# PCM2704_Test_v1.net
KiCad netlist of a schematic drawn in EAGLE
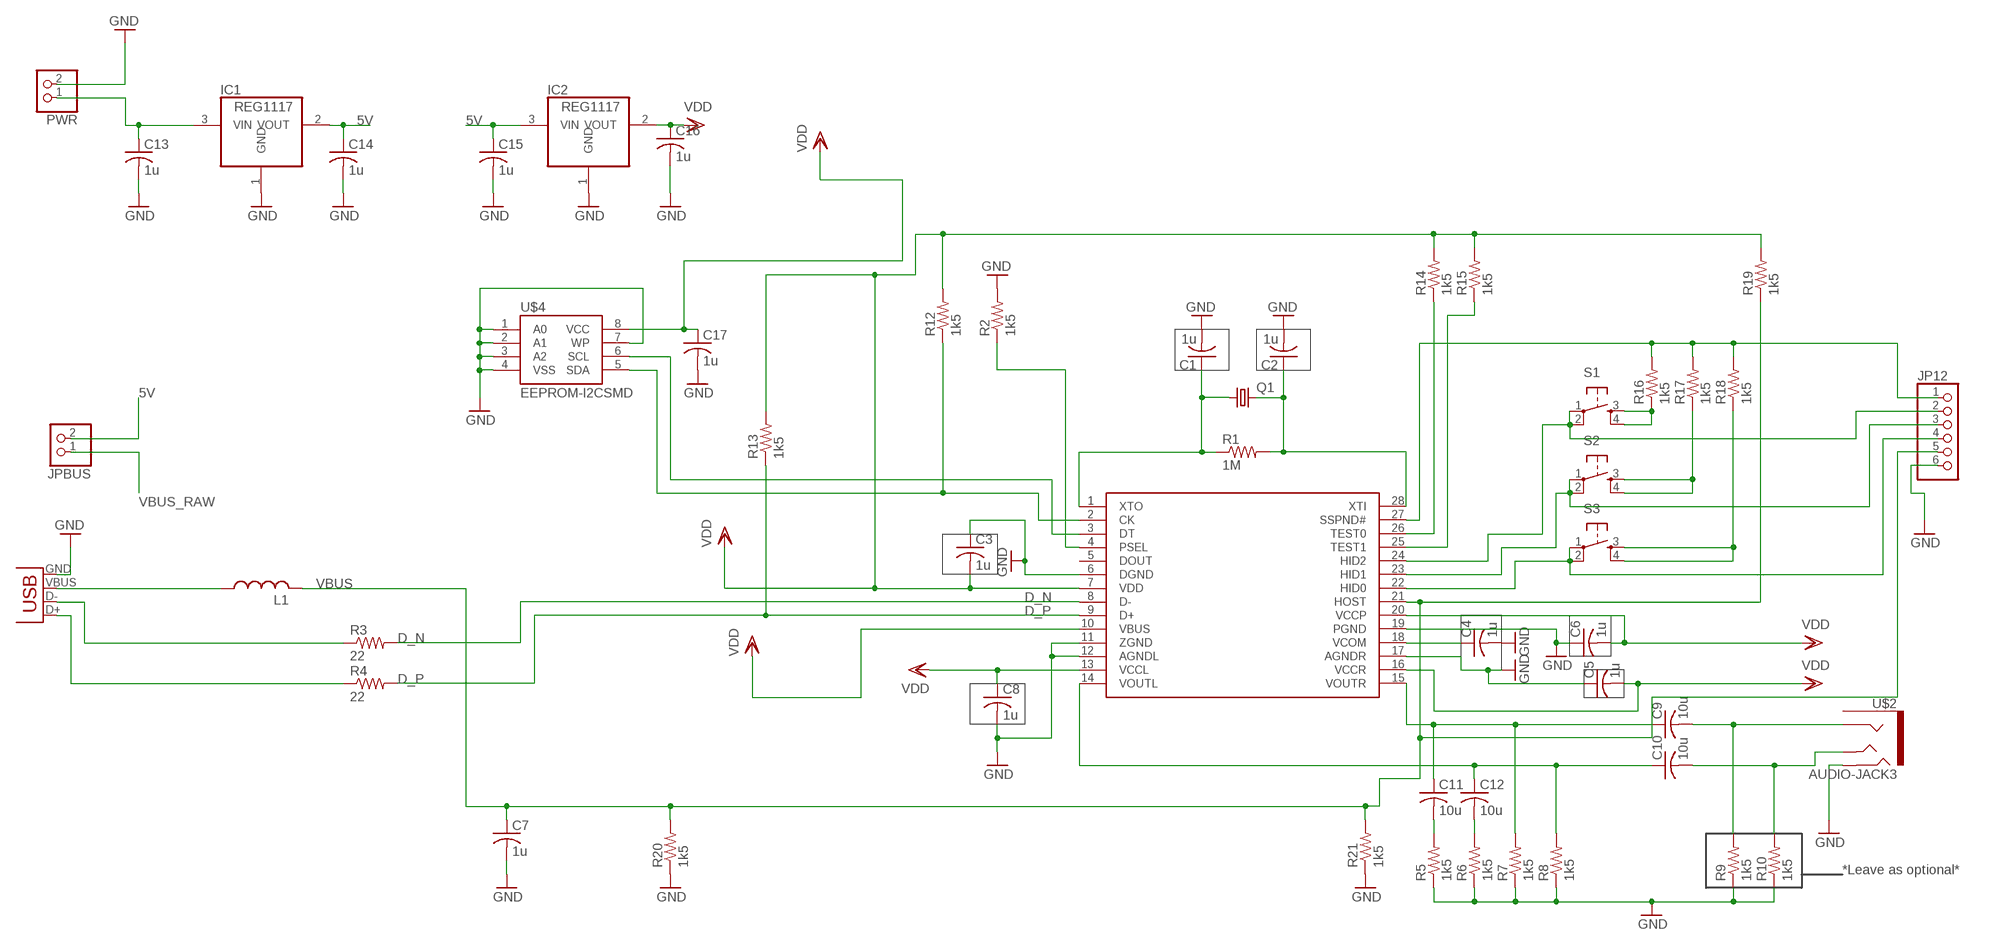
[diagram p0: schematic, sheet 1]

(export (version "E")
  (design (tool "Eeschema 10.0.6"))
  (components
    (comp (ref "C1")
      (value "1u")
      (footprint "eagle-import:C0402")
      (libsource (lib "eagle-import") (part "C-USC0402"))
    )
    (comp (ref "C2")
      (value "1u")
      (footprint "eagle-import:C0402")
      (libsource (lib "eagle-import") (part "C-USC0402"))
    )
    (comp (ref "C3")
      (value "1u")
      (footprint "eagle-import:C0402")
      (libsource (lib "eagle-import") (part "C-USC0402"))
    )
    (comp (ref "C4")
      (value "1u")
      (footprint "eagle-import:C0402")
      (libsource (lib "eagle-import") (part "C-USC0402"))
    )
    (comp (ref "C5")
      (value "1u")
      (footprint "eagle-import:C0402")
      (libsource (lib "eagle-import") (part "C-USC0402"))
    )
    (comp (ref "C6")
      (value "1u")
      (footprint "eagle-import:C0402")
      (libsource (lib "eagle-import") (part "C-USC0402"))
    )
    (comp (ref "C7")
      (value "1u")
      (footprint "eagle-import:C0402")
      (libsource (lib "eagle-import") (part "C-USC0402"))
    )
    (comp (ref "C8")
      (value "1u")
      (footprint "eagle-import:C0402")
      (libsource (lib "eagle-import") (part "C-USC0402"))
    )
    (comp (ref "C9")
      (value "10u")
      (footprint "eagle-import:C0805")
      (libsource (lib "eagle-import") (part "C-USC0805"))
    )
    (comp (ref "C10")
      (value "10u")
      (footprint "eagle-import:C0805")
      (libsource (lib "eagle-import") (part "C-USC0805"))
    )
    (comp (ref "C11")
      (value "10u")
      (footprint "eagle-import:C0805")
      (libsource (lib "eagle-import") (part "C-USC0805"))
    )
    (comp (ref "C12")
      (value "10u")
      (footprint "eagle-import:C0805")
      (libsource (lib "eagle-import") (part "C-USC0805"))
    )
    (comp (ref "C13")
      (value "1u")
      (footprint "eagle-import:C0805")
      (libsource (lib "eagle-import") (part "C-USC0805"))
    )
    (comp (ref "C14")
      (value "1u")
      (footprint "eagle-import:C0805")
      (libsource (lib "eagle-import") (part "C-USC0805"))
    )
    (comp (ref "C15")
      (value "1u")
      (footprint "eagle-import:C0805")
      (libsource (lib "eagle-import") (part "C-USC0805"))
    )
    (comp (ref "C16")
      (value "1u")
      (footprint "eagle-import:C0805")
      (libsource (lib "eagle-import") (part "C-USC0805"))
    )
    (comp (ref "C17")
      (value "1u")
      (footprint "eagle-import:C0402")
      (libsource (lib "eagle-import") (part "C-USC0402"))
    )
    (comp (ref "IC1")
      (value "REG1117")
      (footprint "eagle-import:SOT223")
      (libsource (lib "eagle-import") (part "REG1117"))
    )
    (comp (ref "IC2")
      (value "REG1117")
      (footprint "eagle-import:SOT223")
      (libsource (lib "eagle-import") (part "REG1117"))
    )
    (comp (ref "JP12")
      (value "PINHD-1X6")
      (footprint "eagle-import:1X06")
      (libsource (lib "eagle-import") (part "PINHD-1X6"))
    )
    (comp (ref "JPBUS")
      (value "PINHD-1X2")
      (footprint "eagle-import:1X02")
      (libsource (lib "eagle-import") (part "PINHD-1X2"))
    )
    (comp (ref "L1")
      (value "L-USL3225M")
      (footprint "eagle-import:L3225M")
      (libsource (lib "eagle-import") (part "L-USL3225M"))
    )
    (comp (ref "PWR")
      (value "PINHD-1X2")
      (footprint "eagle-import:1X02")
      (libsource (lib "eagle-import") (part "PINHD-1X2"))
    )
    (comp (ref "Q1")
      (value "CRYSTALHC49US")
      (footprint "eagle-import:HC49US")
      (libsource (lib "eagle-import") (part "CRYSTALHC49US"))
    )
    (comp (ref "R1")
      (value "1M")
      (footprint "eagle-import:R0603")
      (libsource (lib "eagle-import") (part "R-US_R0603"))
    )
    (comp (ref "R2")
      (value "1k5")
      (footprint "eagle-import:R0603")
      (libsource (lib "eagle-import") (part "R-US_R0603"))
    )
    (comp (ref "R3")
      (value "22")
      (footprint "eagle-import:R0603")
      (libsource (lib "eagle-import") (part "R-US_R0603"))
    )
    (comp (ref "R4")
      (value "22")
      (footprint "eagle-import:R0603")
      (libsource (lib "eagle-import") (part "R-US_R0603"))
    )
    (comp (ref "R5")
      (value "1k5")
      (footprint "eagle-import:R0805")
      (libsource (lib "eagle-import") (part "R-US_R0805"))
    )
    (comp (ref "R6")
      (value "1k5")
      (footprint "eagle-import:R0805")
      (libsource (lib "eagle-import") (part "R-US_R0805"))
    )
    (comp (ref "R7")
      (value "1k5")
      (footprint "eagle-import:R0805")
      (libsource (lib "eagle-import") (part "R-US_R0805"))
    )
    (comp (ref "R8")
      (value "1k5")
      (footprint "eagle-import:R0805")
      (libsource (lib "eagle-import") (part "R-US_R0805"))
    )
    (comp (ref "R9")
      (value "1k5")
      (footprint "eagle-import:R0805")
      (libsource (lib "eagle-import") (part "R-US_R0805"))
    )
    (comp (ref "R10")
      (value "1k5")
      (footprint "eagle-import:R0805")
      (libsource (lib "eagle-import") (part "R-US_R0805"))
    )
    (comp (ref "R12")
      (value "1k5")
      (footprint "eagle-import:R0603")
      (libsource (lib "eagle-import") (part "R-US_R0603"))
    )
    (comp (ref "R13")
      (value "1k5")
      (footprint "eagle-import:R0603")
      (libsource (lib "eagle-import") (part "R-US_R0603"))
    )
    (comp (ref "R14")
      (value "1k5")
      (footprint "eagle-import:R0603")
      (libsource (lib "eagle-import") (part "R-US_R0603"))
    )
    (comp (ref "R15")
      (value "1k5")
      (footprint "eagle-import:R0603")
      (libsource (lib "eagle-import") (part "R-US_R0603"))
    )
    (comp (ref "R16")
      (value "1k5")
      (footprint "eagle-import:R0603")
      (libsource (lib "eagle-import") (part "R-US_R0603"))
    )
    (comp (ref "R17")
      (value "1k5")
      (footprint "eagle-import:R0603")
      (libsource (lib "eagle-import") (part "R-US_R0603"))
    )
    (comp (ref "R18")
      (value "1k5")
      (footprint "eagle-import:R0603")
      (libsource (lib "eagle-import") (part "R-US_R0603"))
    )
    (comp (ref "R19")
      (value "1k5")
      (footprint "eagle-import:R0603")
      (libsource (lib "eagle-import") (part "R-US_R0603"))
    )
    (comp (ref "R20")
      (value "1k5")
      (footprint "eagle-import:R0603")
      (libsource (lib "eagle-import") (part "R-US_R0603"))
    )
    (comp (ref "R21")
      (value "1k5")
      (footprint "eagle-import:R0603")
      (libsource (lib "eagle-import") (part "R-US_R0603"))
    )
    (comp (ref "S1")
      (value "TAC_SWITCHSMD")
      (footprint "eagle-import:TACTILE_SWITCH_SMD")
      (libsource (lib "eagle-import") (part "TAC_SWITCHSMD"))
    )
    (comp (ref "S2")
      (value "TAC_SWITCHSMD")
      (footprint "eagle-import:TACTILE_SWITCH_SMD")
      (libsource (lib "eagle-import") (part "TAC_SWITCHSMD"))
    )
    (comp (ref "S3")
      (value "TAC_SWITCHSMD")
      (footprint "eagle-import:TACTILE_SWITCH_SMD")
      (libsource (lib "eagle-import") (part "TAC_SWITCHSMD"))
    )
    (comp (ref "U$1")
      (value "PCM2704C")
      (footprint "eagle-import:PCM2704C")
      (libsource (lib "eagle-import") (part "PCM2704C"))
    )
    (comp (ref "U$2")
      (value "AUDIO-JACK3")
      (footprint "eagle-import:AUDIO-JACK-TRRS-SMD")
      (libsource (lib "eagle-import") (part "AUDIO-JACK3"))
    )
    (comp (ref "U$4")
      (value "EEPROM-I2CSMD")
      (footprint "eagle-import:SO08")
      (libsource (lib "eagle-import") (part "EEPROM-I2CSMD"))
    )
    (comp (ref "X1")
      (value "USB-MB-S")
      (footprint "eagle-import:USB-MB-S")
      (libsource (lib "eagle-import") (part "USB-MB-S"))
    )
  )
  (nets
    (net (code "1") (name "/5V") (class "Default")
      (node (ref "C14") (pin "1") (pinfunction "1_1") (pintype "passive"))
      (node (ref "C15") (pin "1") (pinfunction "1_1") (pintype "passive"))
      (node (ref "IC1") (pin "2") (pinfunction "VOUT_2") (pintype "output"))
      (node (ref "IC2") (pin "3") (pinfunction "VIN_3") (pintype "input"))
      (node (ref "JPBUS") (pin "2") (pinfunction "2_2") (pintype "passive"))
    )
    (net (code "2") (name "/D_N") (class "Default")
      (node (ref "R3") (pin "2") (pinfunction "2_2") (pintype "passive"))
      (node (ref "U$1") (pin "8") (pinfunction "D-_8") (pintype "bidirectional"))
    )
    (net (code "3") (name "/D_P") (class "Default")
      (node (ref "R13") (pin "1") (pinfunction "1_1") (pintype "passive"))
      (node (ref "R4") (pin "2") (pinfunction "2_2") (pintype "passive"))
      (node (ref "U$1") (pin "9") (pinfunction "D+_9") (pintype "bidirectional"))
    )
    (net (code "4") (name "/VBUS") (class "Default")
      (node (ref "C7") (pin "1") (pinfunction "1_1") (pintype "passive"))
      (node (ref "JP12") (pin "5") (pinfunction "5_5") (pintype "passive"))
      (node (ref "L1") (pin "2") (pinfunction "2_2") (pintype "passive"))
      (node (ref "R19") (pin "1") (pinfunction "1_1") (pintype "passive"))
      (node (ref "R20") (pin "2") (pinfunction "2_2") (pintype "passive"))
      (node (ref "R21") (pin "2") (pinfunction "2_2") (pintype "passive"))
      (node (ref "U$1") (pin "21") (pinfunction "HOST_21") (pintype "bidirectional"))
    )
    (net (code "5") (name "/VBUS_RAW") (class "Default")
      (node (ref "JPBUS") (pin "1") (pinfunction "1_1") (pintype "passive"))
      (node (ref "L1") (pin "1") (pinfunction "1_1") (pintype "passive"))
      (node (ref "X1") (pin "VBUS") (pinfunction "VBUS_VBUS") (pintype "bidirectional"))
    )
    (net (code "6") (name "GND") (class "Default")
      (node (ref "C1") (pin "2") (pinfunction "2_2") (pintype "passive"))
      (node (ref "C13") (pin "2") (pinfunction "2_2") (pintype "passive"))
      (node (ref "C14") (pin "2") (pinfunction "2_2") (pintype "passive"))
      (node (ref "C15") (pin "2") (pinfunction "2_2") (pintype "passive"))
      (node (ref "C16") (pin "2") (pinfunction "2_2") (pintype "passive"))
      (node (ref "C17") (pin "2") (pinfunction "2_2") (pintype "passive"))
      (node (ref "C2") (pin "2") (pinfunction "2_2") (pintype "passive"))
      (node (ref "C3") (pin "1") (pinfunction "1_1") (pintype "passive"))
      (node (ref "C4") (pin "2") (pinfunction "2_2") (pintype "passive"))
      (node (ref "C5") (pin "1") (pinfunction "1_1") (pintype "passive"))
      (node (ref "C6") (pin "1") (pinfunction "1_1") (pintype "passive"))
      (node (ref "C7") (pin "2") (pinfunction "2_2") (pintype "passive"))
      (node (ref "C8") (pin "2") (pinfunction "2_2") (pintype "passive"))
      (node (ref "IC1") (pin "1") (pinfunction "GND_1") (pintype "power_in"))
      (node (ref "IC2") (pin "1") (pinfunction "GND_1") (pintype "power_in"))
      (node (ref "JP12") (pin "6") (pinfunction "6_6") (pintype "passive"))
      (node (ref "PWR") (pin "2") (pinfunction "2_2") (pintype "passive"))
      (node (ref "R10") (pin "1") (pinfunction "1_1") (pintype "passive"))
      (node (ref "R2") (pin "2") (pinfunction "2_2") (pintype "passive"))
      (node (ref "R20") (pin "1") (pinfunction "1_1") (pintype "passive"))
      (node (ref "R21") (pin "1") (pinfunction "1_1") (pintype "passive"))
      (node (ref "R5") (pin "1") (pinfunction "1_1") (pintype "passive"))
      (node (ref "R6") (pin "1") (pinfunction "1_1") (pintype "passive"))
      (node (ref "R7") (pin "1") (pinfunction "1_1") (pintype "passive"))
      (node (ref "R8") (pin "1") (pinfunction "1_1") (pintype "passive"))
      (node (ref "R9") (pin "1") (pinfunction "1_1") (pintype "passive"))
      (node (ref "U$1") (pin "11") (pinfunction "ZGND_11") (pintype "bidirectional"))
      (node (ref "U$1") (pin "12") (pinfunction "AGNDL_12") (pintype "bidirectional"))
      (node (ref "U$1") (pin "17") (pinfunction "AGNDR_17") (pintype "bidirectional"))
      (node (ref "U$1") (pin "19") (pinfunction "PGND_19") (pintype "bidirectional"))
      (node (ref "U$1") (pin "6") (pinfunction "DGND_6") (pintype "bidirectional"))
      (node (ref "U$2") (pin "RING2") (pinfunction "RING2_RING2") (pintype "bidirectional"))
      (node (ref "U$4") (pin "1") (pinfunction "A0_1") (pintype "bidirectional"))
      (node (ref "U$4") (pin "2") (pinfunction "A1_2") (pintype "bidirectional"))
      (node (ref "U$4") (pin "3") (pinfunction "A2_3") (pintype "bidirectional"))
      (node (ref "U$4") (pin "4") (pinfunction "VSS_4") (pintype "power_in"))
      (node (ref "U$4") (pin "7") (pinfunction "WP_7") (pintype "bidirectional"))
      (node (ref "X1") (pin "GND") (pinfunction "GND_GND") (pintype "bidirectional"))
    )
    (net (code "7") (name "Net-(C9-Pad2)") (class "Default")
      (node (ref "C9") (pin "2") (pinfunction "2_2") (pintype "passive"))
      (node (ref "R9") (pin "2") (pinfunction "2_2") (pintype "passive"))
      (node (ref "U$2") (pin "RING1") (pinfunction "RING1_RING1") (pintype "bidirectional"))
    )
    (net (code "8") (name "Net-(C10-Pad2)") (class "Default")
      (node (ref "C10") (pin "2") (pinfunction "2_2") (pintype "passive"))
      (node (ref "R10") (pin "2") (pinfunction "2_2") (pintype "passive"))
      (node (ref "U$2") (pin "TIP") (pinfunction "TIP_TIP") (pintype "bidirectional"))
    )
    (net (code "9") (name "Net-(C11-Pad2)") (class "Default")
      (node (ref "C11") (pin "2") (pinfunction "2_2") (pintype "passive"))
      (node (ref "R5") (pin "2") (pinfunction "2_2") (pintype "passive"))
    )
    (net (code "10") (name "Net-(C12-Pad2)") (class "Default")
      (node (ref "C12") (pin "2") (pinfunction "2_2") (pintype "passive"))
      (node (ref "R6") (pin "2") (pinfunction "2_2") (pintype "passive"))
    )
    (net (code "11") (name "Net-(IC1-VIN)") (class "Default")
      (node (ref "C13") (pin "1") (pinfunction "1_1") (pintype "passive"))
      (node (ref "IC1") (pin "3") (pinfunction "VIN_3") (pintype "input"))
      (node (ref "PWR") (pin "1") (pinfunction "1_1") (pintype "passive"))
    )
    (net (code "12") (name "Net-(R3-Pad1)") (class "Default")
      (node (ref "R3") (pin "1") (pinfunction "1_1") (pintype "passive"))
      (node (ref "X1") (pin "D-") (pinfunction "D-_D-") (pintype "bidirectional"))
    )
    (net (code "13") (name "Net-(R4-Pad1)") (class "Default")
      (node (ref "R4") (pin "1") (pinfunction "1_1") (pintype "passive"))
      (node (ref "X1") (pin "D+") (pinfunction "D+_D+") (pintype "bidirectional"))
    )
    (net (code "14") (name "Net-(R16-Pad1)") (class "Default")
      (node (ref "R16") (pin "1") (pinfunction "1_1") (pintype "passive"))
      (node (ref "S1") (pin "3") (pinfunction "3_3") (pintype "passive"))
      (node (ref "S1") (pin "4") (pinfunction "4_4") (pintype "passive"))
    )
    (net (code "15") (name "Net-(R17-Pad1)") (class "Default")
      (node (ref "R17") (pin "1") (pinfunction "1_1") (pintype "passive"))
      (node (ref "S2") (pin "3") (pinfunction "3_3") (pintype "passive"))
      (node (ref "S2") (pin "4") (pinfunction "4_4") (pintype "passive"))
    )
    (net (code "16") (name "Net-(R18-Pad1)") (class "Default")
      (node (ref "R18") (pin "1") (pinfunction "1_1") (pintype "passive"))
      (node (ref "S3") (pin "3") (pinfunction "3_3") (pintype "passive"))
      (node (ref "S3") (pin "4") (pinfunction "4_4") (pintype "passive"))
    )
    (net (code "17") (name "Net-(U$1-CK)") (class "Default")
      (node (ref "R12") (pin "1") (pinfunction "1_1") (pintype "passive"))
      (node (ref "U$1") (pin "2") (pinfunction "CK_2") (pintype "bidirectional"))
      (node (ref "U$4") (pin "5") (pinfunction "SDA_5") (pintype "bidirectional"))
    )
    (net (code "18") (name "Net-(U$1-DT)") (class "Default")
      (node (ref "U$1") (pin "3") (pinfunction "DT_3") (pintype "bidirectional"))
      (node (ref "U$4") (pin "6") (pinfunction "SCL_6") (pintype "bidirectional"))
    )
    (net (code "19") (name "Net-(U$1-HID0)") (class "Default")
      (node (ref "JP12") (pin "4") (pinfunction "4_4") (pintype "passive"))
      (node (ref "S3") (pin "1") (pinfunction "1_1") (pintype "passive"))
      (node (ref "S3") (pin "2") (pinfunction "2_2") (pintype "passive"))
      (node (ref "U$1") (pin "22") (pinfunction "HID0_22") (pintype "bidirectional"))
    )
    (net (code "20") (name "Net-(U$1-HID1)") (class "Default")
      (node (ref "JP12") (pin "3") (pinfunction "3_3") (pintype "passive"))
      (node (ref "S2") (pin "1") (pinfunction "1_1") (pintype "passive"))
      (node (ref "S2") (pin "2") (pinfunction "2_2") (pintype "passive"))
      (node (ref "U$1") (pin "23") (pinfunction "HID1_23") (pintype "bidirectional"))
    )
    (net (code "21") (name "Net-(U$1-HID2)") (class "Default")
      (node (ref "JP12") (pin "2") (pinfunction "2_2") (pintype "passive"))
      (node (ref "S1") (pin "1") (pinfunction "1_1") (pintype "passive"))
      (node (ref "S1") (pin "2") (pinfunction "2_2") (pintype "passive"))
      (node (ref "U$1") (pin "24") (pinfunction "HID2_24") (pintype "bidirectional"))
    )
    (net (code "22") (name "Net-(U$1-PSEL)") (class "Default")
      (node (ref "R2") (pin "1") (pinfunction "1_1") (pintype "passive"))
      (node (ref "U$1") (pin "4") (pinfunction "PSEL_4") (pintype "bidirectional"))
    )
    (net (code "23") (name "Net-(U$1-SSPND#)") (class "Default")
      (node (ref "JP12") (pin "1") (pinfunction "1_1") (pintype "passive"))
      (node (ref "R16") (pin "2") (pinfunction "2_2") (pintype "passive"))
      (node (ref "R17") (pin "2") (pinfunction "2_2") (pintype "passive"))
      (node (ref "R18") (pin "2") (pinfunction "2_2") (pintype "passive"))
      (node (ref "U$1") (pin "27") (pinfunction "SSPND#_27") (pintype "bidirectional"))
    )
    (net (code "24") (name "Net-(U$1-TEST0)") (class "Default")
      (node (ref "R14") (pin "1") (pinfunction "1_1") (pintype "passive"))
      (node (ref "U$1") (pin "26") (pinfunction "TEST0_26") (pintype "bidirectional"))
    )
    (net (code "25") (name "Net-(U$1-TEST1)") (class "Default")
      (node (ref "R15") (pin "1") (pinfunction "1_1") (pintype "passive"))
      (node (ref "U$1") (pin "25") (pinfunction "TEST1_25") (pintype "bidirectional"))
    )
    (net (code "26") (name "Net-(U$1-VCOM)") (class "Default")
      (node (ref "C4") (pin "1") (pinfunction "1_1") (pintype "passive"))
      (node (ref "U$1") (pin "18") (pinfunction "VCOM_18") (pintype "bidirectional"))
    )
    (net (code "27") (name "Net-(U$1-VOUTL)") (class "Default")
      (node (ref "C10") (pin "1") (pinfunction "1_1") (pintype "passive"))
      (node (ref "C12") (pin "1") (pinfunction "1_1") (pintype "passive"))
      (node (ref "R8") (pin "2") (pinfunction "2_2") (pintype "passive"))
      (node (ref "U$1") (pin "14") (pinfunction "VOUTL_14") (pintype "bidirectional"))
    )
    (net (code "28") (name "Net-(U$1-VOUTR)") (class "Default")
      (node (ref "C11") (pin "1") (pinfunction "1_1") (pintype "passive"))
      (node (ref "C9") (pin "1") (pinfunction "1_1") (pintype "passive"))
      (node (ref "R7") (pin "2") (pinfunction "2_2") (pintype "passive"))
      (node (ref "U$1") (pin "15") (pinfunction "VOUTR_15") (pintype "bidirectional"))
    )
    (net (code "29") (name "Net-(U$1-XTI)") (class "Default")
      (node (ref "C2") (pin "1") (pinfunction "1_1") (pintype "passive"))
      (node (ref "Q1") (pin "2") (pinfunction "2_2") (pintype "passive"))
      (node (ref "R1") (pin "2") (pinfunction "2_2") (pintype "passive"))
      (node (ref "U$1") (pin "28") (pinfunction "XTI_28") (pintype "bidirectional"))
    )
    (net (code "30") (name "Net-(U$1-XTO)") (class "Default")
      (node (ref "C1") (pin "1") (pinfunction "1_1") (pintype "passive"))
      (node (ref "Q1") (pin "1") (pinfunction "1_1") (pintype "passive"))
      (node (ref "R1") (pin "1") (pinfunction "1_1") (pintype "passive"))
      (node (ref "U$1") (pin "1") (pinfunction "XTO_1") (pintype "bidirectional"))
    )
    (net (code "31") (name "VDD") (class "Default")
      (node (ref "C16") (pin "1") (pinfunction "1_1") (pintype "passive"))
      (node (ref "C17") (pin "1") (pinfunction "1_1") (pintype "passive"))
      (node (ref "C3") (pin "2") (pinfunction "2_2") (pintype "passive"))
      (node (ref "C5") (pin "2") (pinfunction "2_2") (pintype "passive"))
      (node (ref "C6") (pin "2") (pinfunction "2_2") (pintype "passive"))
      (node (ref "C8") (pin "1") (pinfunction "1_1") (pintype "passive"))
      (node (ref "IC2") (pin "2") (pinfunction "VOUT_2") (pintype "output"))
      (node (ref "R12") (pin "2") (pinfunction "2_2") (pintype "passive"))
      (node (ref "R13") (pin "2") (pinfunction "2_2") (pintype "passive"))
      (node (ref "R14") (pin "2") (pinfunction "2_2") (pintype "passive"))
      (node (ref "R15") (pin "2") (pinfunction "2_2") (pintype "passive"))
      (node (ref "R19") (pin "2") (pinfunction "2_2") (pintype "passive"))
      (node (ref "U$1") (pin "10") (pinfunction "VBUS_10") (pintype "bidirectional"))
      (node (ref "U$1") (pin "13") (pinfunction "VCCL_13") (pintype "bidirectional"))
      (node (ref "U$1") (pin "16") (pinfunction "VCCR_16") (pintype "bidirectional"))
      (node (ref "U$1") (pin "20") (pinfunction "VCCP_20") (pintype "bidirectional"))
      (node (ref "U$1") (pin "7") (pinfunction "VDD_7") (pintype "bidirectional"))
      (node (ref "U$4") (pin "8") (pinfunction "VCC_8") (pintype "power_in"))
    )
    (net (code "32") (name "unconnected-(U$1-DOUT-Pad5)") (class "Default")
      (node (ref "U$1") (pin "5") (pinfunction "DOUT_5") (pintype "bidirectional"))
    )
    (net (code "33") (name "unconnected-(U$2-PadEARTH)") (class "Default")
      (node (ref "U$2") (pin "EARTH") (pinfunction "EARTH_EARTH") (pintype "bidirectional"))
    )
  )
)
